# Display_Sheet.net
KiCad netlist of a schematic drawn in Altium Designer
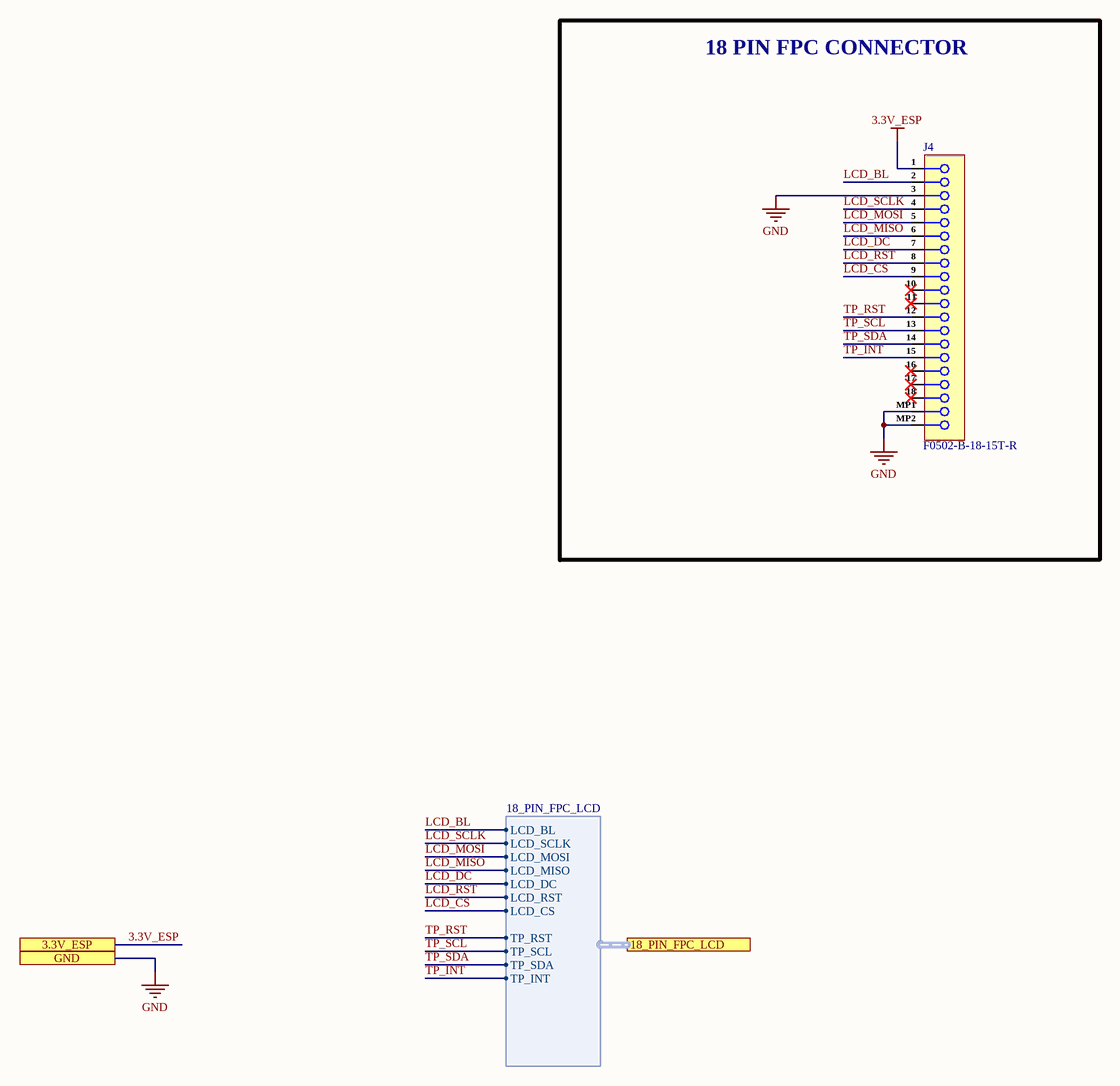
[diagram p0: Display_Sheet.SchDoc]

(export (version "E")
  (design (tool "Eeschema 10.0.6"))
  (components
    (comp (ref "J4")
      (value "F0502-B-18-15T-R")
      (footprint "F0502-B-18-15T-R")
      (description "Clamshell -25℃~+85℃ 18P Bottom Contact Surface Mount 0.5mm SMD,P=0.5mm FFC/FPC Connectors ROHS")
      (fields (field (name "MANUFACTURER") "XFCN") (field (name "LCSC PART NUMBER") "C2889974"))
      (libsource (lib "eSpark Libraries") (part "F0502-B-18-15T-R"))
    )
  )
  (nets
    (net (code "2") (name "/LCD_BL") (class "Default")
      (node (ref "J4") (pin "2") (pinfunction "2_2") (pintype "passive"))
    )
    (net (code "3") (name "/LCD_CS") (class "Default")
      (node (ref "J4") (pin "9") (pinfunction "9_9") (pintype "passive"))
    )
    (net (code "4") (name "/LCD_DC") (class "Default")
      (node (ref "J4") (pin "7") (pinfunction "7_7") (pintype "passive"))
    )
    (net (code "5") (name "/LCD_MISO") (class "Default")
      (node (ref "J4") (pin "6") (pinfunction "6_6") (pintype "passive"))
    )
    (net (code "6") (name "/LCD_MOSI") (class "Default")
      (node (ref "J4") (pin "5") (pinfunction "5_5") (pintype "passive"))
    )
    (net (code "7") (name "/LCD_RST") (class "Default")
      (node (ref "J4") (pin "8") (pinfunction "8_8") (pintype "passive"))
    )
    (net (code "8") (name "/LCD_SCLK") (class "Default")
      (node (ref "J4") (pin "4") (pinfunction "4_4") (pintype "passive"))
    )
    (net (code "9") (name "/TP_INT") (class "Default")
      (node (ref "J4") (pin "15") (pinfunction "15_15") (pintype "passive"))
    )
    (net (code "10") (name "/TP_RST") (class "Default")
      (node (ref "J4") (pin "12") (pinfunction "12_12") (pintype "passive"))
    )
    (net (code "11") (name "/TP_SCL") (class "Default")
      (node (ref "J4") (pin "13") (pinfunction "13_13") (pintype "passive"))
    )
    (net (code "12") (name "/TP_SDA") (class "Default")
      (node (ref "J4") (pin "14") (pinfunction "14_14") (pintype "passive"))
    )
    (net (code "14") (name "3.3V_ESP") (class "Default")
      (node (ref "J4") (pin "1") (pinfunction "1_1") (pintype "passive"))
    )
    (net (code "15") (name "GND") (class "Default")
      (node (ref "J4") (pin "3") (pinfunction "3_3") (pintype "passive"))
      (node (ref "J4") (pin "MP1") (pinfunction "MP1_MP1") (pintype "passive"))
      (node (ref "J4") (pin "MP2") (pinfunction "MP2_MP2") (pintype "passive"))
    )
    (net (code "16") (name "unconnected-(J4-Pad10)") (class "Default")
      (node (ref "J4") (pin "10") (pinfunction "10_10") (pintype "passive+no_connect"))
    )
    (net (code "17") (name "unconnected-(J4-Pad11)") (class "Default")
      (node (ref "J4") (pin "11") (pinfunction "11_11") (pintype "passive+no_connect"))
    )
    (net (code "18") (name "unconnected-(J4-Pad16)") (class "Default")
      (node (ref "J4") (pin "16") (pinfunction "16_16") (pintype "passive+no_connect"))
    )
    (net (code "19") (name "unconnected-(J4-Pad17)") (class "Default")
      (node (ref "J4") (pin "17") (pinfunction "17_17") (pintype "passive+no_connect"))
    )
    (net (code "20") (name "unconnected-(J4-Pad18)") (class "Default")
      (node (ref "J4") (pin "18") (pinfunction "18_18") (pintype "passive+no_connect"))
    )
  )
)
